# Memory.net
KiCad netlist of a schematic drawn in Altium Designer
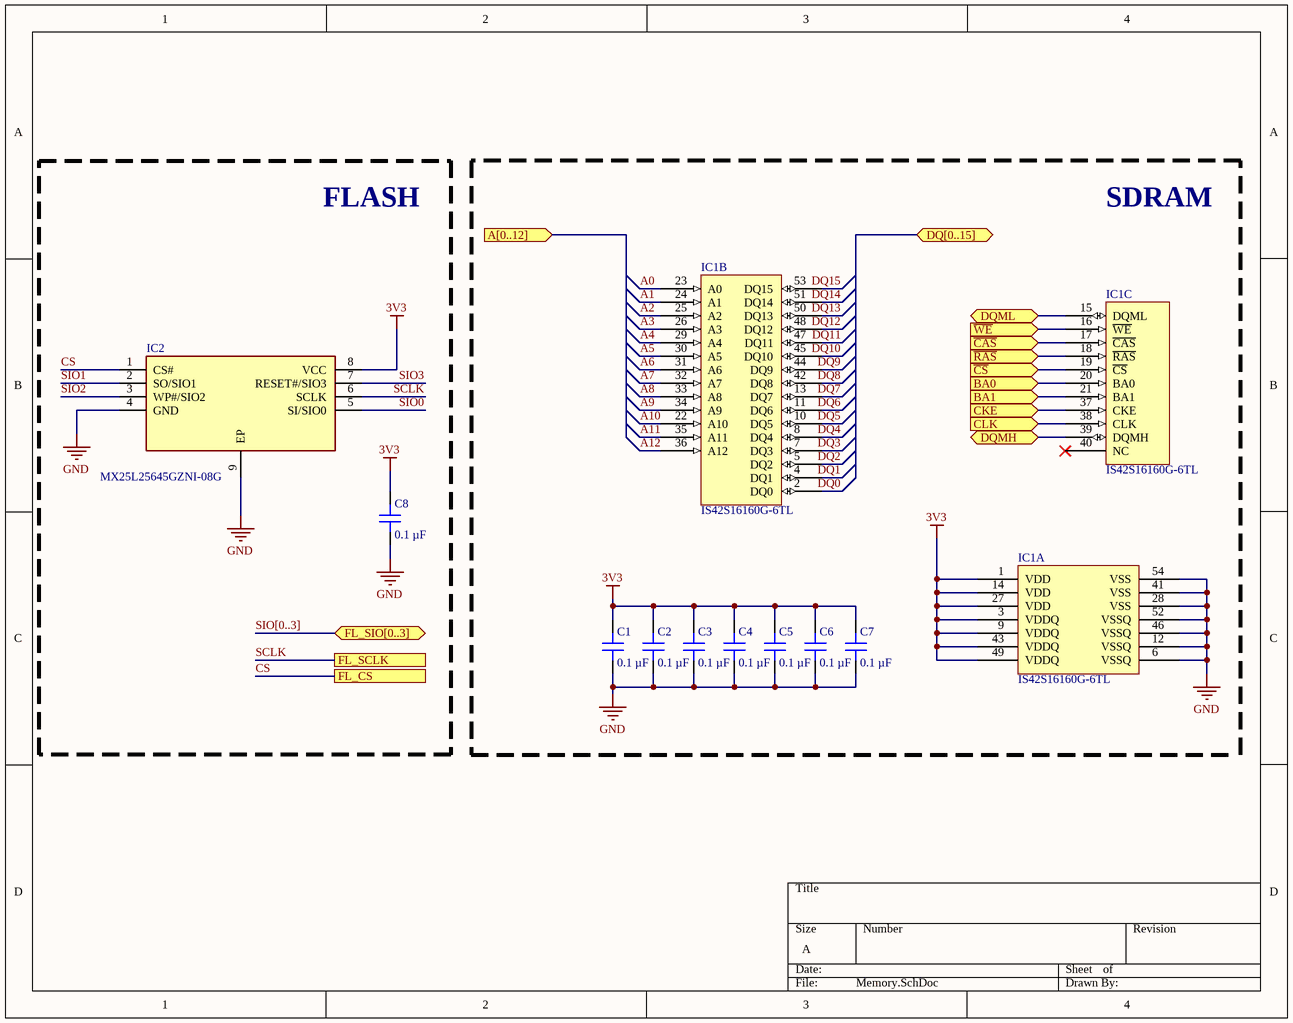
[diagram p0: Memory.SchDoc]

(export (version "E")
  (design (tool "Eeschema 10.0.6"))
  (components
    (comp (ref "C1")
      (value "0.1 µF")
      (footprint "CAP 0603_1608")
      (description "CAP CER 0.1UF 100V X7R 0603")
      (fields
        (field (name "PART NUMBER") "0603B104K101CT")
        (field (name "MANUFACTURER") "Walsin Technology Corporation")
      )
      (libsource (lib "Celestial Altium Library - altium_library") (part "Capacitor"))
    )
    (comp (ref "C2")
      (value "0.1 µF")
      (footprint "CAP 0603_1608")
      (description "CAP CER 0.1UF 100V X7R 0603")
      (fields
        (field (name "PART NUMBER") "0603B104K101CT")
        (field (name "MANUFACTURER") "Walsin Technology Corporation")
      )
      (libsource (lib "Celestial Altium Library - altium_library") (part "Capacitor"))
    )
    (comp (ref "C3")
      (value "0.1 µF")
      (footprint "CAP 0603_1608")
      (description "CAP CER 0.1UF 100V X7R 0603")
      (fields
        (field (name "PART NUMBER") "0603B104K101CT")
        (field (name "MANUFACTURER") "Walsin Technology Corporation")
      )
      (libsource (lib "Celestial Altium Library - altium_library") (part "Capacitor"))
    )
    (comp (ref "C4")
      (value "0.1 µF")
      (footprint "CAP 0603_1608")
      (description "CAP CER 0.1UF 100V X7R 0603")
      (fields
        (field (name "PART NUMBER") "0603B104K101CT")
        (field (name "MANUFACTURER") "Walsin Technology Corporation")
      )
      (libsource (lib "Celestial Altium Library - altium_library") (part "Capacitor"))
    )
    (comp (ref "C5")
      (value "0.1 µF")
      (footprint "CAP 0603_1608")
      (description "CAP CER 0.1UF 100V X7R 0603")
      (fields
        (field (name "PART NUMBER") "0603B104K101CT")
        (field (name "MANUFACTURER") "Walsin Technology Corporation")
      )
      (libsource (lib "Celestial Altium Library - altium_library") (part "Capacitor"))
    )
    (comp (ref "C6")
      (value "0.1 µF")
      (footprint "CAP 0603_1608")
      (description "CAP CER 0.1UF 100V X7R 0603")
      (fields
        (field (name "PART NUMBER") "0603B104K101CT")
        (field (name "MANUFACTURER") "Walsin Technology Corporation")
      )
      (libsource (lib "Celestial Altium Library - altium_library") (part "Capacitor"))
    )
    (comp (ref "C7")
      (value "0.1 µF")
      (footprint "CAP 0603_1608")
      (description "CAP CER 0.1UF 100V X7R 0603")
      (fields
        (field (name "PART NUMBER") "0603B104K101CT")
        (field (name "MANUFACTURER") "Walsin Technology Corporation")
      )
      (libsource (lib "Celestial Altium Library - altium_library") (part "Capacitor"))
    )
    (comp (ref "C8")
      (value "0.1 µF")
      (footprint "CAP 0603_1608")
      (description "CAP CER 0.1UF 100V X7R 0603")
      (fields
        (field (name "PART NUMBER") "0603B104K101CT")
        (field (name "MANUFACTURER") "Walsin Technology Corporation")
      )
      (libsource (lib "Celestial Altium Library - altium_library") (part "Capacitor"))
    )
    (comp (ref "IC1")
      (value "IS42S16160G-6TL")
      (footprint "SamacSys:SOP80P1176X120-54N")
      (description "Integrated Circuit")
      (fields (field (name "MOUSER PART NUMBER") "870-IS42S16160G-6TL"))
      (libsource (lib "SamacSys") (part "IS42S16160G-6TL"))
    )
    (comp (ref "IC2")
      (value "MX25L25645GZNI-08G")
      (footprint "SamacSys:SON127P600X500X80-9N-D")
      (description "Integrated Circuit")
      (libsource (lib "*") (part "MX25L25645GZNI-08G"))
    )
  )
  (nets
    (net (code "1") (name "/A0") (class "Default")
      (node (ref "IC1") (pin "23") (pinfunction "A0_23") (pintype "input"))
    )
    (net (code "2") (name "/A1") (class "Default")
      (node (ref "IC1") (pin "24") (pinfunction "A1_24") (pintype "input"))
    )
    (net (code "3") (name "/A2") (class "Default")
      (node (ref "IC1") (pin "25") (pinfunction "A2_25") (pintype "input"))
    )
    (net (code "4") (name "/A3") (class "Default")
      (node (ref "IC1") (pin "26") (pinfunction "A3_26") (pintype "input"))
    )
    (net (code "5") (name "/A4") (class "Default")
      (node (ref "IC1") (pin "29") (pinfunction "A4_29") (pintype "input"))
    )
    (net (code "6") (name "/A5") (class "Default")
      (node (ref "IC1") (pin "30") (pinfunction "A5_30") (pintype "input"))
    )
    (net (code "7") (name "/A6") (class "Default")
      (node (ref "IC1") (pin "31") (pinfunction "A6_31") (pintype "input"))
    )
    (net (code "8") (name "/A7") (class "Default")
      (node (ref "IC1") (pin "32") (pinfunction "A7_32") (pintype "input"))
    )
    (net (code "9") (name "/A8") (class "Default")
      (node (ref "IC1") (pin "33") (pinfunction "A8_33") (pintype "input"))
    )
    (net (code "10") (name "/A9") (class "Default")
      (node (ref "IC1") (pin "34") (pinfunction "A9_34") (pintype "input"))
    )
    (net (code "11") (name "/A10") (class "Default")
      (node (ref "IC1") (pin "22") (pinfunction "A10_22") (pintype "input"))
    )
    (net (code "12") (name "/A11") (class "Default")
      (node (ref "IC1") (pin "35") (pinfunction "A11_35") (pintype "input"))
    )
    (net (code "13") (name "/A12") (class "Default")
      (node (ref "IC1") (pin "36") (pinfunction "A12_36") (pintype "input"))
    )
    (net (code "14") (name "/BA0") (class "Default")
      (node (ref "IC1") (pin "20") (pinfunction "BA0_20") (pintype "input"))
    )
    (net (code "15") (name "/BA1") (class "Default")
      (node (ref "IC1") (pin "21") (pinfunction "BA1_21") (pintype "input"))
    )
    (net (code "16") (name "/CKE") (class "Default")
      (node (ref "IC1") (pin "37") (pinfunction "CKE_37") (pintype "input"))
    )
    (net (code "17") (name "/CLK") (class "Default")
      (node (ref "IC1") (pin "38") (pinfunction "CLK_38") (pintype "input"))
    )
    (net (code "18") (name "/CS") (class "Default")
      (node (ref "IC2") (pin "1") (pinfunction "CS#_1") (pintype "passive"))
    )
    (net (code "19") (name "/DQ0") (class "Default")
      (node (ref "IC1") (pin "2") (pinfunction "DQ0_2") (pintype "bidirectional"))
    )
    (net (code "20") (name "/DQ1") (class "Default")
      (node (ref "IC1") (pin "4") (pinfunction "DQ1_4") (pintype "bidirectional"))
    )
    (net (code "21") (name "/DQ2") (class "Default")
      (node (ref "IC1") (pin "5") (pinfunction "DQ2_5") (pintype "bidirectional"))
    )
    (net (code "22") (name "/DQ3") (class "Default")
      (node (ref "IC1") (pin "7") (pinfunction "DQ3_7") (pintype "bidirectional"))
    )
    (net (code "23") (name "/DQ4") (class "Default")
      (node (ref "IC1") (pin "8") (pinfunction "DQ4_8") (pintype "bidirectional"))
    )
    (net (code "24") (name "/DQ5") (class "Default")
      (node (ref "IC1") (pin "10") (pinfunction "DQ5_10") (pintype "bidirectional"))
    )
    (net (code "25") (name "/DQ6") (class "Default")
      (node (ref "IC1") (pin "11") (pinfunction "DQ6_11") (pintype "bidirectional"))
    )
    (net (code "26") (name "/DQ7") (class "Default")
      (node (ref "IC1") (pin "13") (pinfunction "DQ7_13") (pintype "bidirectional"))
    )
    (net (code "27") (name "/DQ8") (class "Default")
      (node (ref "IC1") (pin "42") (pinfunction "DQ8_42") (pintype "bidirectional"))
    )
    (net (code "28") (name "/DQ9") (class "Default")
      (node (ref "IC1") (pin "44") (pinfunction "DQ9_44") (pintype "bidirectional"))
    )
    (net (code "29") (name "/DQ10") (class "Default")
      (node (ref "IC1") (pin "45") (pinfunction "DQ10_45") (pintype "bidirectional"))
    )
    (net (code "30") (name "/DQ11") (class "Default")
      (node (ref "IC1") (pin "47") (pinfunction "DQ11_47") (pintype "bidirectional"))
    )
    (net (code "31") (name "/DQ12") (class "Default")
      (node (ref "IC1") (pin "48") (pinfunction "DQ12_48") (pintype "bidirectional"))
    )
    (net (code "32") (name "/DQ13") (class "Default")
      (node (ref "IC1") (pin "50") (pinfunction "DQ13_50") (pintype "bidirectional"))
    )
    (net (code "33") (name "/DQ14") (class "Default")
      (node (ref "IC1") (pin "51") (pinfunction "DQ14_51") (pintype "bidirectional"))
    )
    (net (code "34") (name "/DQ15") (class "Default")
      (node (ref "IC1") (pin "53") (pinfunction "DQ15_53") (pintype "bidirectional"))
    )
    (net (code "35") (name "/DQMH") (class "Default")
      (node (ref "IC1") (pin "39") (pinfunction "DQMH_39") (pintype "bidirectional"))
    )
    (net (code "36") (name "/DQML") (class "Default")
      (node (ref "IC1") (pin "15") (pinfunction "DQML_15") (pintype "bidirectional"))
    )
    (net (code "38") (name "/SCLK") (class "Default")
      (node (ref "IC2") (pin "6") (pinfunction "SCLK_6") (pintype "passive"))
    )
    (net (code "39") (name "/SIO0") (class "Default")
      (node (ref "IC2") (pin "5") (pinfunction "SI/SIO0_5") (pintype "passive"))
    )
    (net (code "40") (name "/SIO1") (class "Default")
      (node (ref "IC2") (pin "2") (pinfunction "SO/SIO1_2") (pintype "passive"))
    )
    (net (code "41") (name "/SIO2") (class "Default")
      (node (ref "IC2") (pin "3") (pinfunction "WP#/SIO2_3") (pintype "passive"))
    )
    (net (code "42") (name "/SIO3") (class "Default")
      (node (ref "IC2") (pin "7") (pinfunction "RESET#/SIO3_7") (pintype "passive"))
    )
    (net (code "45") (name "/~{CAS}") (class "Default")
      (node (ref "IC1") (pin "17") (pinfunction "CAS_17") (pintype "input"))
    )
    (net (code "46") (name "/~{CS}") (class "Default")
      (node (ref "IC1") (pin "19") (pinfunction "CS_19") (pintype "input"))
    )
    (net (code "47") (name "/~{RAS}") (class "Default")
      (node (ref "IC1") (pin "18") (pinfunction "RAS_18") (pintype "input"))
    )
    (net (code "48") (name "/~{WE}") (class "Default")
      (node (ref "IC1") (pin "16") (pinfunction "WE_16") (pintype "input"))
    )
    (net (code "49") (name "3V3") (class "Default")
      (node (ref "C1") (pin "2") (pinfunction "2_2") (pintype "passive"))
      (node (ref "C2") (pin "2") (pinfunction "2_2") (pintype "passive"))
      (node (ref "C3") (pin "2") (pinfunction "2_2") (pintype "passive"))
      (node (ref "C4") (pin "2") (pinfunction "2_2") (pintype "passive"))
      (node (ref "C5") (pin "2") (pinfunction "2_2") (pintype "passive"))
      (node (ref "C6") (pin "2") (pinfunction "2_2") (pintype "passive"))
      (node (ref "C7") (pin "2") (pinfunction "2_2") (pintype "passive"))
      (node (ref "C8") (pin "2") (pinfunction "2_2") (pintype "passive"))
      (node (ref "IC1") (pin "1") (pinfunction "VDD_1") (pintype "power_in"))
      (node (ref "IC1") (pin "14") (pinfunction "VDD_14") (pintype "power_in"))
      (node (ref "IC1") (pin "27") (pinfunction "VDD_27") (pintype "power_in"))
      (node (ref "IC1") (pin "3") (pinfunction "VDDQ_3") (pintype "power_in"))
      (node (ref "IC1") (pin "43") (pinfunction "VDDQ_43") (pintype "power_in"))
      (node (ref "IC1") (pin "49") (pinfunction "VDDQ_49") (pintype "power_in"))
      (node (ref "IC1") (pin "9") (pinfunction "VDDQ_9") (pintype "power_in"))
      (node (ref "IC2") (pin "8") (pinfunction "VCC_8") (pintype "passive"))
    )
    (net (code "50") (name "GND") (class "Default")
      (node (ref "C1") (pin "1") (pinfunction "1_1") (pintype "passive"))
      (node (ref "C2") (pin "1") (pinfunction "1_1") (pintype "passive"))
      (node (ref "C3") (pin "1") (pinfunction "1_1") (pintype "passive"))
      (node (ref "C4") (pin "1") (pinfunction "1_1") (pintype "passive"))
      (node (ref "C5") (pin "1") (pinfunction "1_1") (pintype "passive"))
      (node (ref "C6") (pin "1") (pinfunction "1_1") (pintype "passive"))
      (node (ref "C7") (pin "1") (pinfunction "1_1") (pintype "passive"))
      (node (ref "C8") (pin "1") (pinfunction "1_1") (pintype "passive"))
      (node (ref "IC1") (pin "12") (pinfunction "VSSQ_12") (pintype "input"))
      (node (ref "IC1") (pin "28") (pinfunction "VSS_28") (pintype "input"))
      (node (ref "IC1") (pin "41") (pinfunction "VSS_41") (pintype "input"))
      (node (ref "IC1") (pin "46") (pinfunction "VSSQ_46") (pintype "input"))
      (node (ref "IC1") (pin "52") (pinfunction "VSSQ_52") (pintype "input"))
      (node (ref "IC1") (pin "54") (pinfunction "VSS_54") (pintype "input"))
      (node (ref "IC1") (pin "6") (pinfunction "VSSQ_6") (pintype "input"))
      (node (ref "IC2") (pin "4") (pinfunction "GND_4") (pintype "passive"))
      (node (ref "IC2") (pin "9") (pinfunction "EP_9") (pintype "passive"))
    )
    (net (code "51") (name "unconnected-(IC1C-NC-Pad40)") (class "Default")
      (node (ref "IC1") (pin "40") (pinfunction "NC_40") (pintype "passive+no_connect"))
    )
  )
)
